# 3-Wifi-SD.net
KiCad netlist of a schematic drawn in Altium Designer
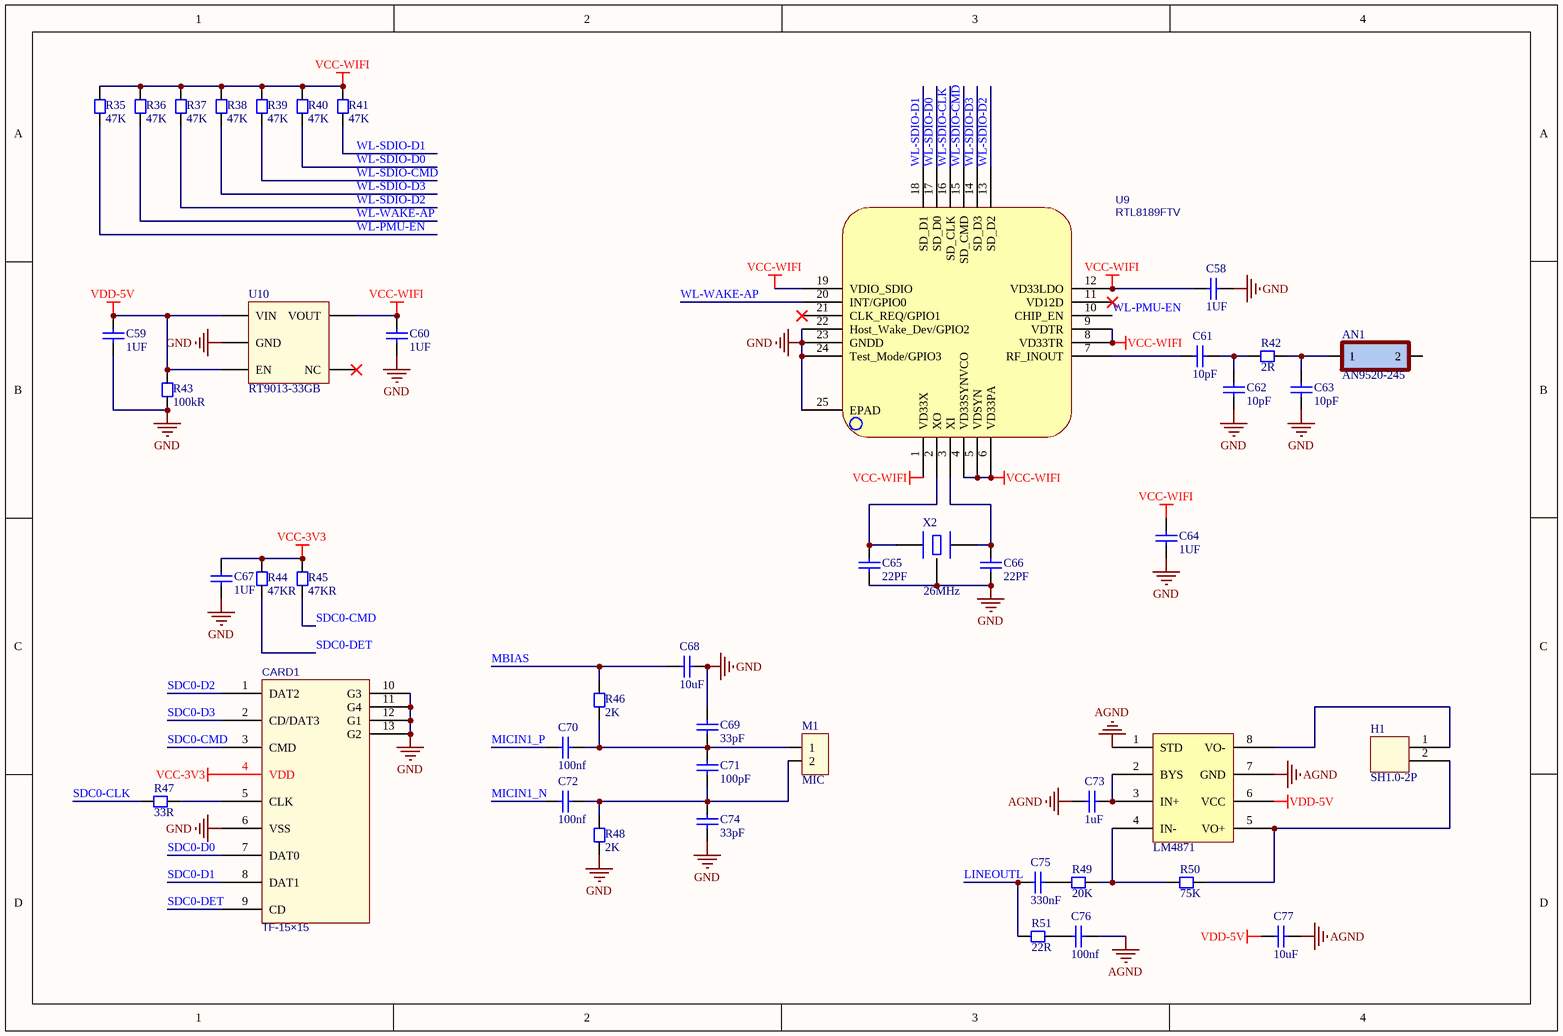
[diagram p0: 3-Wifi-SD.SchDoc]

(export (version "E")
  (design (tool "Eeschema 10.0.6"))
  (components
    (comp (ref "AN1")
      (value "AN9520-245")
      (footprint "AN-5120")
      (description "2.4G全向天线 蓝牙天线 陶瓷贴片 WIFI内置")
      (libsource (lib "tianxiaohua_Schlib") (part "AN9520-245"))
    )
    (comp (ref "C58")
      (value "1UF")
      (footprint "CC1005-0402")
      (description "贴片电容")
      (libsource (lib "tianxiaohua_Schlib") (part "Chip capacitor"))
    )
    (comp (ref "C59")
      (value "1UF")
      (footprint "CC1005-0402")
      (description "贴片电容")
      (libsource (lib "tianxiaohua_Schlib") (part "Chip capacitor"))
    )
    (comp (ref "C60")
      (value "1UF")
      (footprint "CC1005-0402")
      (description "贴片电容")
      (libsource (lib "tianxiaohua_Schlib") (part "Chip capacitor"))
    )
    (comp (ref "C61")
      (value "10pF")
      (footprint "CC1005-0402")
      (description "贴片电容")
      (libsource (lib "tianxiaohua_Schlib") (part "Chip capacitor"))
    )
    (comp (ref "C62")
      (value "10pF")
      (footprint "CC1005-0402")
      (description "贴片电容")
      (libsource (lib "tianxiaohua_Schlib") (part "Chip capacitor"))
    )
    (comp (ref "C63")
      (value "10pF")
      (footprint "CC1005-0402")
      (description "贴片电容")
      (libsource (lib "tianxiaohua_Schlib") (part "Chip capacitor"))
    )
    (comp (ref "C64")
      (value "1UF")
      (footprint "CC1005-0402")
      (description "贴片电容")
      (libsource (lib "tianxiaohua_Schlib") (part "Chip capacitor"))
    )
    (comp (ref "C65")
      (value "22PF")
      (footprint "CC1005-0402")
      (description "贴片电容")
      (libsource (lib "tianxiaohua_Schlib") (part "Chip capacitor"))
    )
    (comp (ref "C66")
      (value "22PF")
      (footprint "CC1005-0402")
      (description "贴片电容")
      (libsource (lib "tianxiaohua_Schlib") (part "Chip capacitor"))
    )
    (comp (ref "C67")
      (value "1UF")
      (footprint "CC1005-0402")
      (description "贴片电容")
      (libsource (lib "tianxiaohua_Schlib") (part "Chip capacitor"))
    )
    (comp (ref "C68")
      (value "10uF")
      (footprint "CC1608-0603")
      (description "贴片电容")
      (libsource (lib "tianxiaohua_Schlib") (part "Chip capacitor"))
    )
    (comp (ref "C69")
      (value "33pF")
      (footprint "CC1005-0402")
      (description "贴片电容")
      (libsource (lib "tianxiaohua_Schlib") (part "Chip capacitor"))
    )
    (comp (ref "C70")
      (value "100nf")
      (footprint "CC1005-0402")
      (description "贴片电容")
      (libsource (lib "tianxiaohua_Schlib") (part "Chip capacitor"))
    )
    (comp (ref "C71")
      (value "100pF")
      (footprint "CC1005-0402")
      (description "贴片电容")
      (libsource (lib "tianxiaohua_Schlib") (part "Chip capacitor"))
    )
    (comp (ref "C72")
      (value "100nf")
      (footprint "CC1005-0402")
      (description "贴片电容")
      (libsource (lib "tianxiaohua_Schlib") (part "Chip capacitor"))
    )
    (comp (ref "C73")
      (value "1uF")
      (footprint "CC1005-0402")
      (description "贴片电容")
      (libsource (lib "tianxiaohua_Schlib") (part "Chip capacitor"))
    )
    (comp (ref "C74")
      (value "33pF")
      (footprint "CC1005-0402")
      (description "贴片电容")
      (libsource (lib "tianxiaohua_Schlib") (part "Chip capacitor"))
    )
    (comp (ref "C75")
      (value "330nF")
      (footprint "CC1005-0402")
      (description "贴片电容")
      (libsource (lib "tianxiaohua_Schlib") (part "Chip capacitor"))
    )
    (comp (ref "C76")
      (value "100nf")
      (footprint "CC1005-0402")
      (description "贴片电容")
      (libsource (lib "tianxiaohua_Schlib") (part "Chip capacitor"))
    )
    (comp (ref "C77")
      (value "10uF")
      (footprint "CC1608-0603")
      (description "贴片电容")
      (libsource (lib "tianxiaohua_Schlib") (part "Chip capacitor"))
    )
    (comp (ref "CARD1")
      (value "TF-15×15")
      (footprint "TF-SMD_TF-15-15")
      (description "TF卡卡座 https://item.szlcsc.com/112422.html")
      (fields (field (name "BOM_SUPPLIER PART") "C111196"))
      (libsource (lib "tianxiaohua_Schlib") (part "TF-15×15"))
    )
    (comp (ref "H1")
      (value "SH1.0-2P")
      (footprint "SH1.0-2P")
      (libsource (lib "tianxiaohua_Schlib") (part "SH1.0-2P"))
    )
    (comp (ref "M1")
      (value "MIC")
      (footprint "MIC6*2.2mm")
      (description "驻体麦克风")
      (libsource (lib "tianxiaohua_Schlib") (part "MIC"))
    )
    (comp (ref "R35")
      (value "47K")
      (footprint "CR1005-0402")
      (description "贴片电阻")
      (libsource (lib "tianxiaohua_Schlib") (part "Chip resistor"))
    )
    (comp (ref "R36")
      (value "47K")
      (footprint "CR1005-0402")
      (description "贴片电阻")
      (libsource (lib "tianxiaohua_Schlib") (part "Chip resistor"))
    )
    (comp (ref "R37")
      (value "47K")
      (footprint "CR1005-0402")
      (description "贴片电阻")
      (libsource (lib "tianxiaohua_Schlib") (part "Chip resistor"))
    )
    (comp (ref "R38")
      (value "47K")
      (footprint "CR1005-0402")
      (description "贴片电阻")
      (libsource (lib "tianxiaohua_Schlib") (part "Chip resistor"))
    )
    (comp (ref "R39")
      (value "47K")
      (footprint "CR1005-0402")
      (description "贴片电阻")
      (libsource (lib "tianxiaohua_Schlib") (part "Chip resistor"))
    )
    (comp (ref "R40")
      (value "47K")
      (footprint "CR1005-0402")
      (description "贴片电阻")
      (libsource (lib "tianxiaohua_Schlib") (part "Chip resistor"))
    )
    (comp (ref "R41")
      (value "47K")
      (footprint "CR1005-0402")
      (description "贴片电阻")
      (libsource (lib "tianxiaohua_Schlib") (part "Chip resistor"))
    )
    (comp (ref "R42")
      (value "2R")
      (footprint "CR1005-0402")
      (description "贴片电阻")
      (libsource (lib "") (part "Chip resistor_2"))
    )
    (comp (ref "R43")
      (value "100kR")
      (footprint "CR1005-0402")
      (description "贴片电阻")
      (libsource (lib "tianxiaohua_Schlib") (part "Chip resistor"))
    )
    (comp (ref "R44")
      (value "47KR")
      (footprint "CR1005-0402")
      (description "贴片电阻")
      (libsource (lib "tianxiaohua_Schlib") (part "Chip resistor"))
    )
    (comp (ref "R45")
      (value "47KR")
      (footprint "CR1005-0402")
      (description "贴片电阻")
      (libsource (lib "tianxiaohua_Schlib") (part "Chip resistor"))
    )
    (comp (ref "R46")
      (value "2K")
      (footprint "CR1005-0402")
      (description "贴片电阻")
      (libsource (lib "tianxiaohua_Schlib") (part "Chip resistor"))
    )
    (comp (ref "R47")
      (value "33R")
      (footprint "CR1005-0402")
      (description "贴片电阻")
      (libsource (lib "") (part "Chip resistor_1"))
    )
    (comp (ref "R48")
      (value "2K")
      (footprint "CR1005-0402")
      (description "贴片电阻")
      (libsource (lib "tianxiaohua_Schlib") (part "Chip resistor"))
    )
    (comp (ref "R49")
      (value "20K")
      (footprint "CR1005-0402")
      (description "贴片电阻")
      (libsource (lib "") (part "Chip resistor_1"))
    )
    (comp (ref "R50")
      (value "75K")
      (footprint "CR1005-0402")
      (description "贴片电阻")
      (libsource (lib "") (part "Chip resistor_1"))
    )
    (comp (ref "R51")
      (value "22R")
      (footprint "CR1005-0402")
      (description "贴片电阻")
      (libsource (lib "") (part "Chip resistor_2"))
    )
    (comp (ref "U0")
      (value "LM4871")
      (footprint "MSOP-8")
      (description "单通道音频放大器")
      (libsource (lib "tianxiaohua_Schlib") (part "LM4871"))
    )
    (comp (ref "U9")
      (value "RTL8189FTV")
      (footprint "QFN24-0404-.5")
      (fields (field (name "CONTRIBUTOR") "Pythoniot"))
      (libsource (lib "tianxiaohua_Schlib") (part "RTL8189FTV"))
    )
    (comp (ref "U10")
      (value "RT9013-33GB")
      (footprint "SOT23-5")
      (description "LDO 2.2-5.2V IN 500Ma OUT SOT23-5")
      (libsource (lib "tianxiaohua_Schlib") (part "RT9013-33GB"))
    )
    (comp (ref "X2")
      (value "26MHz")
      (footprint "XTAL-3225")
      (description "3225封装的晶振")
      (libsource (lib "tianxiaohua_Schlib") (part "XTAL 3225"))
    )
  )
  (nets
    (net (code "1") (name "/LINEOUTL") (class "Default")
      (node (ref "C75") (pin "1") (pinfunction "1_1") (pintype "passive"))
      (node (ref "R51") (pin "1") (pinfunction "1_1") (pintype "passive"))
    )
    (net (code "2") (name "/MBIAS") (class "Default")
      (node (ref "C68") (pin "2") (pinfunction "2_2") (pintype "passive"))
      (node (ref "R46") (pin "2") (pinfunction "2_2") (pintype "passive"))
    )
    (net (code "3") (name "/MICIN1_N") (class "Default")
      (node (ref "C72") (pin "2") (pinfunction "2_2") (pintype "passive"))
    )
    (net (code "4") (name "/MICIN1_P") (class "Default")
      (node (ref "C70") (pin "2") (pinfunction "2_2") (pintype "passive"))
    )
    (net (code "5") (name "/SDC0-CLK") (class "Default")
      (node (ref "R47") (pin "2") (pinfunction "2_2") (pintype "passive"))
    )
    (net (code "6") (name "/SDC0-CMD") (class "Default")
      (node (ref "CARD1") (pin "3") (pinfunction "CMD_3") (pintype "passive"))
      (node (ref "R45") (pin "1") (pinfunction "1_1") (pintype "passive"))
    )
    (net (code "7") (name "/SDC0-D0") (class "Default")
      (node (ref "CARD1") (pin "7") (pinfunction "DAT0_7") (pintype "passive"))
    )
    (net (code "8") (name "/SDC0-D1") (class "Default")
      (node (ref "CARD1") (pin "8") (pinfunction "DAT1_8") (pintype "passive"))
    )
    (net (code "9") (name "/SDC0-D2") (class "Default")
      (node (ref "CARD1") (pin "1") (pinfunction "DAT2_1") (pintype "passive"))
    )
    (net (code "10") (name "/SDC0-D3") (class "Default")
      (node (ref "CARD1") (pin "2") (pinfunction "CD/DAT3_2") (pintype "passive"))
    )
    (net (code "11") (name "/SDC0-DET") (class "Default")
      (node (ref "CARD1") (pin "9") (pinfunction "CD_9") (pintype "passive"))
      (node (ref "R44") (pin "1") (pinfunction "1_1") (pintype "passive"))
    )
    (net (code "12") (name "/WL-PMU-EN") (class "Default")
      (node (ref "R35") (pin "1") (pinfunction "1_1") (pintype "passive"))
      (node (ref "U9") (pin "10") (pinfunction "CHIP_EN_10") (pintype "passive"))
    )
    (net (code "13") (name "/WL-SDIO-CLK") (class "Default")
      (node (ref "U9") (pin "16") (pinfunction "SD_CLK_16") (pintype "passive"))
    )
    (net (code "14") (name "/WL-SDIO-CMD") (class "Default")
      (node (ref "R39") (pin "1") (pinfunction "1_1") (pintype "passive"))
      (node (ref "U9") (pin "15") (pinfunction "SD_CMD_15") (pintype "passive"))
    )
    (net (code "15") (name "/WL-SDIO-D0") (class "Default")
      (node (ref "R40") (pin "1") (pinfunction "1_1") (pintype "passive"))
      (node (ref "U9") (pin "17") (pinfunction "SD_D0_17") (pintype "passive"))
    )
    (net (code "16") (name "/WL-SDIO-D1") (class "Default")
      (node (ref "R41") (pin "1") (pinfunction "1_1") (pintype "passive"))
      (node (ref "U9") (pin "18") (pinfunction "SD_D1_18") (pintype "passive"))
    )
    (net (code "17") (name "/WL-SDIO-D2") (class "Default")
      (node (ref "R37") (pin "1") (pinfunction "1_1") (pintype "passive"))
      (node (ref "U9") (pin "13") (pinfunction "SD_D2_13") (pintype "passive"))
    )
    (net (code "18") (name "/WL-SDIO-D3") (class "Default")
      (node (ref "R38") (pin "1") (pinfunction "1_1") (pintype "passive"))
      (node (ref "U9") (pin "14") (pinfunction "SD_D3_14") (pintype "passive"))
    )
    (net (code "19") (name "/WL-WAKE-AP") (class "Default")
      (node (ref "R36") (pin "1") (pinfunction "1_1") (pintype "passive"))
      (node (ref "U9") (pin "20") (pinfunction "INT/GPIO0_20") (pintype "passive"))
    )
    (net (code "20") (name "AGND") (class "Default")
      (node (ref "C73") (pin "1") (pinfunction "1_1") (pintype "passive"))
      (node (ref "C76") (pin "1") (pinfunction "1_1") (pintype "passive"))
      (node (ref "C77") (pin "1") (pinfunction "1_1") (pintype "passive"))
      (node (ref "U0") (pin "1") (pinfunction "STD_1") (pintype "passive"))
      (node (ref "U0") (pin "7") (pinfunction "GND_7") (pintype "passive"))
    )
    (net (code "21") (name "GND") (class "Default")
      (node (ref "C58") (pin "2") (pinfunction "2_2") (pintype "passive"))
      (node (ref "C59") (pin "2") (pinfunction "2_2") (pintype "passive"))
      (node (ref "C60") (pin "2") (pinfunction "2_2") (pintype "passive"))
      (node (ref "C62") (pin "2") (pinfunction "2_2") (pintype "passive"))
      (node (ref "C63") (pin "2") (pinfunction "2_2") (pintype "passive"))
      (node (ref "C64") (pin "2") (pinfunction "2_2") (pintype "passive"))
      (node (ref "C65") (pin "1") (pinfunction "1_1") (pintype "passive"))
      (node (ref "C66") (pin "1") (pinfunction "1_1") (pintype "passive"))
      (node (ref "C67") (pin "2") (pinfunction "2_2") (pintype "passive"))
      (node (ref "C68") (pin "1") (pinfunction "1_1") (pintype "passive"))
      (node (ref "C69") (pin "1") (pinfunction "1_1") (pintype "passive"))
      (node (ref "C74") (pin "2") (pinfunction "2_2") (pintype "passive"))
      (node (ref "CARD1") (pin "10") (pinfunction "G3_10") (pintype "passive"))
      (node (ref "CARD1") (pin "11") (pinfunction "G4_11") (pintype "passive"))
      (node (ref "CARD1") (pin "12") (pinfunction "G1_12") (pintype "passive"))
      (node (ref "CARD1") (pin "13") (pinfunction "G2_13") (pintype "passive"))
      (node (ref "CARD1") (pin "6") (pinfunction "VSS_6") (pintype "passive"))
      (node (ref "R43") (pin "1") (pinfunction "1_1") (pintype "passive"))
      (node (ref "R48") (pin "1") (pinfunction "1_1") (pintype "passive"))
      (node (ref "U10") (pin "2") (pinfunction "GND_2") (pintype "passive"))
      (node (ref "U9") (pin "22") (pinfunction "Host_Wake_Dev/GPIO2_22") (pintype "passive"))
      (node (ref "U9") (pin "23") (pinfunction "GNDD_23") (pintype "passive"))
      (node (ref "U9") (pin "24") (pinfunction "Test_Mode/GPIO3_24") (pintype "passive"))
      (node (ref "U9") (pin "25") (pinfunction "EPAD_25") (pintype "passive"))
      (node (ref "X2") (pin "2") (pinfunction "GND_2") (pintype "passive"))
    )
    (net (code "22") (name "Net-(AN1-Pad1)") (class "Default")
      (node (ref "AN1") (pin "1") (pinfunction "1_1") (pintype "passive"))
      (node (ref "C63") (pin "1") (pinfunction "1_1") (pintype "passive"))
      (node (ref "R42") (pin "2") (pinfunction "2_2") (pintype "passive"))
    )
    (net (code "23") (name "Net-(C61-Pad1)") (class "Default")
      (node (ref "C61") (pin "1") (pinfunction "1_1") (pintype "passive"))
      (node (ref "C62") (pin "1") (pinfunction "1_1") (pintype "passive"))
      (node (ref "R42") (pin "1") (pinfunction "1_1") (pintype "passive"))
    )
    (net (code "24") (name "Net-(C69-Pad2)") (class "Default")
      (node (ref "C69") (pin "2") (pinfunction "2_2") (pintype "passive"))
      (node (ref "C70") (pin "1") (pinfunction "1_1") (pintype "passive"))
      (node (ref "C71") (pin "1") (pinfunction "1_1") (pintype "passive"))
      (node (ref "M1") (pin "1") (pinfunction "1_1") (pintype "passive"))
      (node (ref "R46") (pin "1") (pinfunction "1_1") (pintype "passive"))
    )
    (net (code "25") (name "Net-(C71-Pad2)") (class "Default")
      (node (ref "C71") (pin "2") (pinfunction "2_2") (pintype "passive"))
      (node (ref "C72") (pin "1") (pinfunction "1_1") (pintype "passive"))
      (node (ref "C74") (pin "1") (pinfunction "1_1") (pintype "passive"))
      (node (ref "M1") (pin "2") (pinfunction "2_2") (pintype "passive"))
      (node (ref "R48") (pin "2") (pinfunction "2_2") (pintype "passive"))
    )
    (net (code "26") (name "Net-(C75-Pad2)") (class "Default")
      (node (ref "C75") (pin "2") (pinfunction "2_2") (pintype "passive"))
      (node (ref "R49") (pin "2") (pinfunction "2_2") (pintype "passive"))
    )
    (net (code "27") (name "Net-(C76-Pad2)") (class "Default")
      (node (ref "C76") (pin "2") (pinfunction "2_2") (pintype "passive"))
      (node (ref "R51") (pin "2") (pinfunction "2_2") (pintype "passive"))
    )
    (net (code "28") (name "Net-(CARD1-CLK)") (class "Default")
      (node (ref "CARD1") (pin "5") (pinfunction "CLK_5") (pintype "passive"))
      (node (ref "R47") (pin "1") (pinfunction "1_1") (pintype "passive"))
    )
    (net (code "29") (name "Net-(U0-BYS)") (class "Default")
      (node (ref "C73") (pin "2") (pinfunction "2_2") (pintype "passive"))
      (node (ref "U0") (pin "2") (pinfunction "BYS_2") (pintype "passive"))
      (node (ref "U0") (pin "3") (pinfunction "IN+_3") (pintype "passive"))
    )
    (net (code "30") (name "Net-(U0-IN-)") (class "Default")
      (node (ref "R49") (pin "1") (pinfunction "1_1") (pintype "passive"))
      (node (ref "R50") (pin "2") (pinfunction "2_2") (pintype "passive"))
      (node (ref "U0") (pin "4") (pinfunction "IN-_4") (pintype "passive"))
    )
    (net (code "31") (name "Net-(U0-VO+)") (class "Default")
      (node (ref "H1") (pin "2") (pinfunction "2_2") (pintype "passive"))
      (node (ref "R50") (pin "1") (pinfunction "1_1") (pintype "passive"))
      (node (ref "U0") (pin "5") (pinfunction "VO+_5") (pintype "passive"))
    )
    (net (code "32") (name "Net-(U0-VO-)") (class "Default")
      (node (ref "H1") (pin "1") (pintype "passive"))
      (node (ref "U0") (pin "8") (pinfunction "VO-_8") (pintype "passive"))
    )
    (net (code "33") (name "Net-(U9-RF_INOUT)") (class "Default")
      (node (ref "C61") (pin "2") (pinfunction "2_2") (pintype "passive"))
      (node (ref "U9") (pin "7") (pinfunction "RF_INOUT_7") (pintype "passive"))
    )
    (net (code "34") (name "Net-(U9-XI)") (class "Default")
      (node (ref "C66") (pin "2") (pinfunction "2_2") (pintype "passive"))
      (node (ref "U9") (pin "3") (pinfunction "XI_3") (pintype "passive"))
      (node (ref "X2") (pin "3") (pinfunction "OSC2_3") (pintype "passive"))
    )
    (net (code "35") (name "Net-(U9-XO)") (class "Default")
      (node (ref "C65") (pin "2") (pinfunction "2_2") (pintype "passive"))
      (node (ref "U9") (pin "2") (pinfunction "XO_2") (pintype "passive"))
      (node (ref "X2") (pin "1") (pinfunction "OSC1_1") (pintype "passive"))
    )
    (net (code "36") (name "VCC-3V3") (class "Default")
      (node (ref "C67") (pin "1") (pinfunction "1_1") (pintype "passive"))
      (node (ref "CARD1") (pin "4") (pinfunction "VDD_4") (pintype "passive"))
      (node (ref "R44") (pin "2") (pinfunction "2_2") (pintype "passive"))
      (node (ref "R45") (pin "2") (pinfunction "2_2") (pintype "passive"))
    )
    (net (code "37") (name "VCC-WIFI") (class "Default")
      (node (ref "C58") (pin "1") (pinfunction "1_1") (pintype "passive"))
      (node (ref "C60") (pin "1") (pinfunction "1_1") (pintype "passive"))
      (node (ref "C64") (pin "1") (pinfunction "1_1") (pintype "passive"))
      (node (ref "R35") (pin "2") (pinfunction "2_2") (pintype "passive"))
      (node (ref "R36") (pin "2") (pinfunction "2_2") (pintype "passive"))
      (node (ref "R37") (pin "2") (pinfunction "2_2") (pintype "passive"))
      (node (ref "R38") (pin "2") (pinfunction "2_2") (pintype "passive"))
      (node (ref "R39") (pin "2") (pinfunction "2_2") (pintype "passive"))
      (node (ref "R40") (pin "2") (pinfunction "2_2") (pintype "passive"))
      (node (ref "R41") (pin "2") (pinfunction "2_2") (pintype "passive"))
      (node (ref "U10") (pin "5") (pinfunction "VOUT_5") (pintype "passive"))
      (node (ref "U9") (pin "1") (pinfunction "VD33X_1") (pintype "passive"))
      (node (ref "U9") (pin "12") (pinfunction "VD33LDO_12") (pintype "passive"))
      (node (ref "U9") (pin "19") (pinfunction "VDIO_SDIO_19") (pintype "passive"))
      (node (ref "U9") (pin "4") (pinfunction "VD33SYNVCO_4") (pintype "passive"))
      (node (ref "U9") (pin "5") (pinfunction "VDSYN_5") (pintype "passive"))
      (node (ref "U9") (pin "6") (pinfunction "VD33PA_6") (pintype "passive"))
      (node (ref "U9") (pin "8") (pinfunction "VD33TR_8") (pintype "passive"))
      (node (ref "U9") (pin "9") (pinfunction "VDTR_9") (pintype "passive"))
    )
    (net (code "38") (name "VDD-5V") (class "Default")
      (node (ref "C59") (pin "1") (pinfunction "1_1") (pintype "passive"))
      (node (ref "C77") (pin "2") (pinfunction "2_2") (pintype "passive"))
      (node (ref "R43") (pin "2") (pinfunction "2_2") (pintype "passive"))
      (node (ref "U0") (pin "6") (pinfunction "VCC_6") (pintype "passive"))
      (node (ref "U10") (pin "1") (pinfunction "VIN_1") (pintype "passive"))
      (node (ref "U10") (pin "3") (pinfunction "EN_3") (pintype "passive"))
    )
    (net (code "39") (name "unconnected-(AN1-Pad2)") (class "Default")
      (node (ref "AN1") (pin "2") (pinfunction "2_2") (pintype "passive"))
    )
    (net (code "40") (name "unconnected-(U9-CLK_REQ{slash}GPIO1-Pad21)") (class "Default")
      (node (ref "U9") (pin "21") (pinfunction "CLK_REQ/GPIO1_21") (pintype "passive+no_connect"))
    )
    (net (code "41") (name "unconnected-(U9-VD12D-Pad11)") (class "Default")
      (node (ref "U9") (pin "11") (pinfunction "VD12D_11") (pintype "passive+no_connect"))
    )
    (net (code "42") (name "unconnected-(U10-NC-Pad4)") (class "Default")
      (node (ref "U10") (pin "4") (pinfunction "NC_4") (pintype "passive+no_connect"))
    )
  )
)
